# ip_phone_b_miscellaneous.net
KiCad netlist of a schematic drawn in Altium Designer
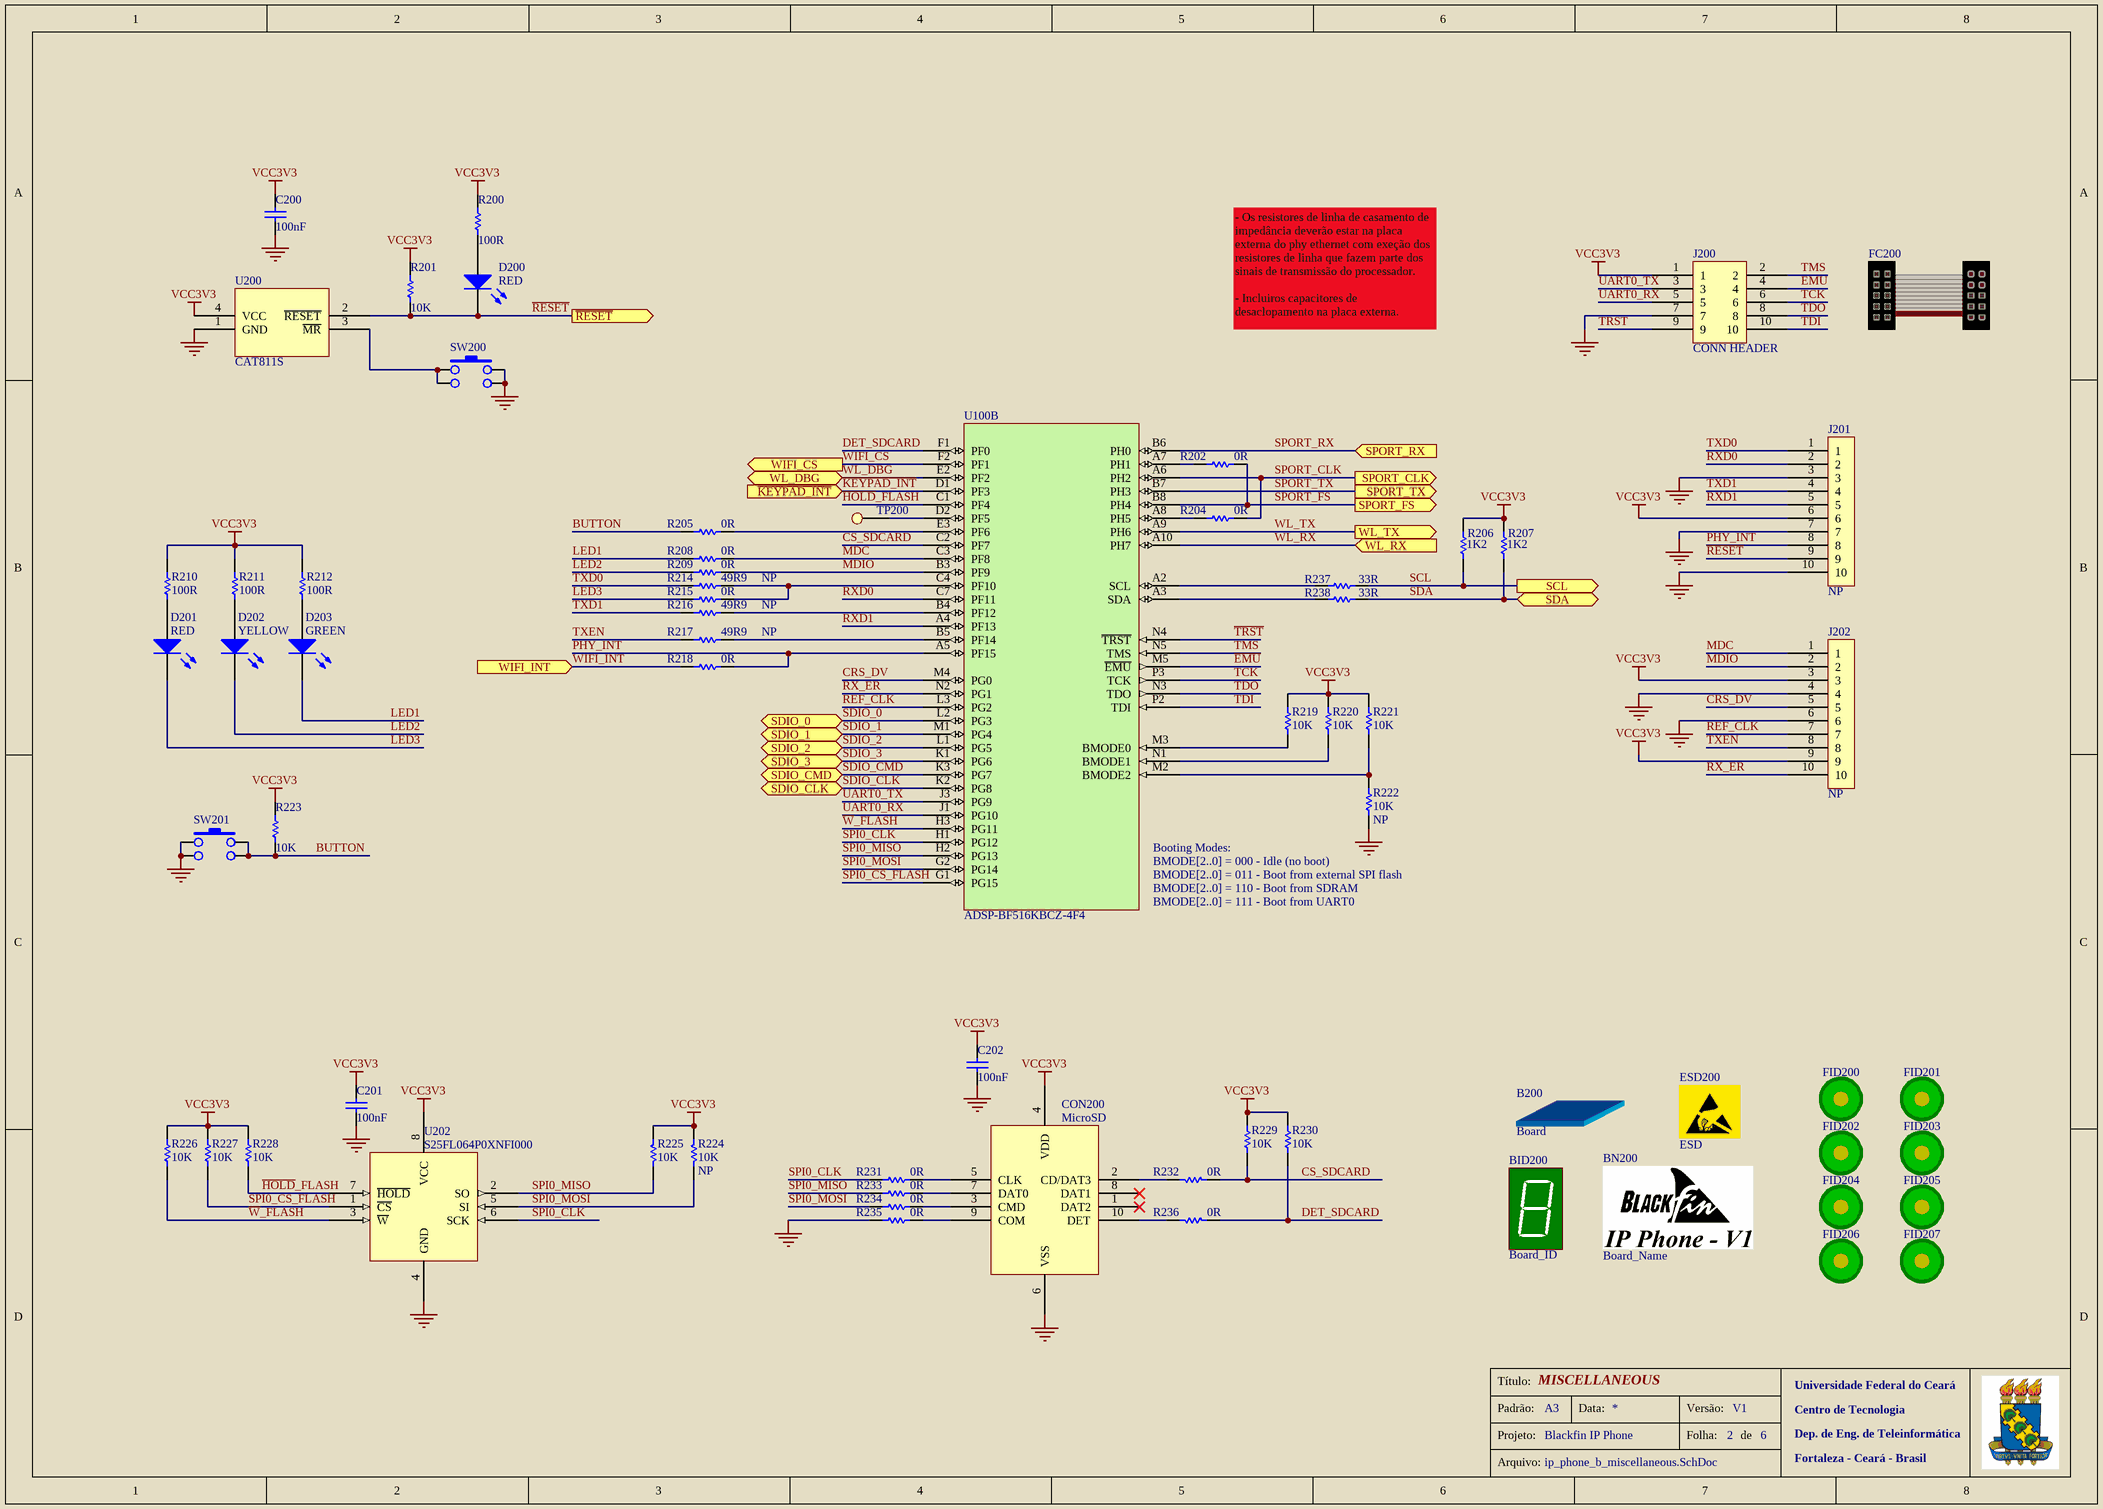
[diagram p0: ip_phone_b_miscellaneous.SchDoc]

(export (version "E")
  (design (tool "Eeschema 10.0.6"))
  (components
    (comp (ref "B200") (value "Board") (libsource (lib "ip_phone") (part "Board")))
    (comp (ref "BID200")
      (value "Board_ID")
      (footprint "ip_phone:BOARD_ID")
      (fields (field (name "EVENDORPART#") "NÃO SE APLICA"))
      (libsource (lib "ip_phone") (part "Board_ID"))
    )
    (comp (ref "BN200")
      (value "Board_Name")
      (footprint "ip_phone:LOGO")
      (fields (field (name "EVENDORPART#") "NÃO SE APLICA"))
      (libsource (lib "ip_phone") (part "Board_Name"))
    )
    (comp (ref "C200")
      (value "100nF")
      (footprint "ip_phone:CC1005-0402")
      (description "MLCC - SMD/SMT 0.1UF 16V 10% 0402")
      (fields (field (name "EVENDORPART#") "810-C1005X7R1C104K") (field (name "MANUFACTURER") "TDK"))
      (libsource (lib "ip_phone") (part "Capacitor"))
    )
    (comp (ref "C201")
      (value "100nF")
      (footprint "ip_phone:CC1005-0402")
      (description "MLCC - SMD/SMT 0.1UF 16V 10% 0402")
      (fields (field (name "EVENDORPART#") "810-C1005X7R1C104K") (field (name "MANUFACTURER") "TDK"))
      (libsource (lib "ip_phone") (part "Capacitor"))
    )
    (comp (ref "C202")
      (value "100nF")
      (footprint "ip_phone:CC1005-0402")
      (description "MLCC - SMD/SMT 0.1UF 16V 10% 0402")
      (fields (field (name "EVENDORPART#") "810-C1005X7R1C104K") (field (name "MANUFACTURER") "TDK"))
      (libsource (lib "ip_phone") (part "Capacitor"))
    )
    (comp (ref "CON200")
      (value "MicroSD")
      (footprint "ip_phone:MICRO_SD")
      (description "CONN MEMORY CARD SD SMD")
      (fields (field (name "MANUFACTURER") "AVX Corporation") (field (name "PART#") "045138008010890+"))
      (libsource (lib "ip_phone") (part "MicroSD"))
    )
    (comp (ref "D200")
      (value "RED")
      (footprint "ip_phone:LED_0603")
      (description "LED")
      (fields (field (name "PART#") "APT1608SURCK") (field (name "MANUFACTURER") "Kingbright"))
      (libsource (lib "ip_phone") (part "LED"))
    )
    (comp (ref "D201")
      (value "RED")
      (footprint "ip_phone:LED 3MM VERMELHO PF-D3")
      (description "LED")
      (fields (field (name "PART#") "TLHR4205") (field (name "MANUFACTURER") "Vishay Semiconductors"))
      (libsource (lib "ip_phone") (part "LED"))
    )
    (comp (ref "D202")
      (value "YELLOW")
      (footprint "ip_phone:LED 3MM AMARELO PF-D3")
      (description "LED")
      (fields (field (name "PART#") "TLHY4205") (field (name "MANUFACTURER") "Vishay Semiconductors"))
      (libsource (lib "ip_phone") (part "LED"))
    )
    (comp (ref "D203")
      (value "GREEN")
      (footprint "ip_phone:LED 3MM VERDE PF-D3")
      (description "LED")
      (fields (field (name "PART#") "TLHG4205") (field (name "MANUFACTURER") "Vishay Semiconductors"))
      (libsource (lib "ip_phone") (part "LED"))
    )
    (comp (ref "ESD200")
      (value "ESD")
      (footprint "ip_phone:ESD")
      (fields (field (name "EVENDORPART#") "NÃO SE APLICA"))
      (libsource (lib "ip_phone") (part "ESD"))
    )
    (comp (ref "FC200")
      (value "Flat Cable")
      (fields (field (name "EVENDORPART#") "SAM8218-ND") (field (name "MANUFACTURER") "Samtec"))
      (libsource (lib "ip_phone") (part "Flat_Cable"))
    )
    (comp (ref "FID200")
      (value "Fiducial")
      (footprint "ip_phone:Fiducial")
      (fields (field (name "EVENDORPART#") "NÃO SE APLICA"))
      (libsource (lib "ip_phone") (part "Fiducial"))
    )
    (comp (ref "FID201")
      (value "Fiducial")
      (footprint "ip_phone:Fiducial")
      (fields (field (name "EVENDORPART#") "NÃO SE APLICA"))
      (libsource (lib "ip_phone") (part "Fiducial"))
    )
    (comp (ref "FID202")
      (value "Fiducial")
      (footprint "ip_phone:Fiducial")
      (fields (field (name "EVENDORPART#") "NÃO SE APLICA"))
      (libsource (lib "ip_phone") (part "Fiducial"))
    )
    (comp (ref "FID203")
      (value "Fiducial")
      (footprint "ip_phone:Fiducial")
      (fields (field (name "EVENDORPART#") "NÃO SE APLICA"))
      (libsource (lib "ip_phone") (part "Fiducial"))
    )
    (comp (ref "FID204")
      (value "Fiducial")
      (footprint "ip_phone:Fiducial")
      (fields (field (name "EVENDORPART#") "NÃO SE APLICA"))
      (libsource (lib "ip_phone") (part "Fiducial"))
    )
    (comp (ref "FID205")
      (value "Fiducial")
      (footprint "ip_phone:Fiducial")
      (fields (field (name "EVENDORPART#") "NÃO SE APLICA"))
      (libsource (lib "ip_phone") (part "Fiducial"))
    )
    (comp (ref "FID206")
      (value "Fiducial")
      (footprint "ip_phone:Fiducial")
      (fields (field (name "EVENDORPART#") "NÃO SE APLICA"))
      (libsource (lib "ip_phone") (part "Fiducial"))
    )
    (comp (ref "FID207")
      (value "Fiducial")
      (footprint "ip_phone:Fiducial")
      (fields (field (name "EVENDORPART#") "NÃO SE APLICA"))
      (libsource (lib "ip_phone") (part "Fiducial"))
    )
    (comp (ref "J200")
      (value "CONN HEADER")
      (footprint "ip_phone:CON_JTAG")
      (description "CONN HEADER .050\" 5x2")
      (fields (field (name "EVENDORPART#") "S9012E-05-ND") (field (name "MANUFACTURER") "Sullins"))
      (libsource (lib "ip_phone") (part "Conector JTAG"))
    )
    (comp (ref "J201")
      (value "CONN HEADER")
      (footprint "ip_phone:CONECTOR_10_PIN")
      (description "CONN HEADER .050\" 10POS PCB GOLD")
      (fields
        (field (name "EVENDORPART#") "S9014E-10-ND")
        (field (name "MANUFACTURER") "Sullins Connector Solutions")
        (field (name "NP") "NP")
      )
      (libsource (lib "ip_phone") (part "Conector 10pin"))
    )
    (comp (ref "J202")
      (value "CONN HEADER")
      (footprint "ip_phone:CONECTOR_10_PIN")
      (description "CONN HEADER .050\" 10POS PCB GOLD")
      (fields
        (field (name "EVENDORPART#") "S9014E-10-ND")
        (field (name "MANUFACTURER") "Sullins Connector Solutions")
        (field (name "NP") "NP")
      )
      (libsource (lib "ip_phone") (part "Conector 10pin"))
    )
    (comp (ref "R200")
      (value "100R")
      (footprint "ip_phone:CR1608-0603")
      (description "Thick Film Resistors 1/16WATT 100R 0402")
      (fields (field (name "EVENDORPART#") "652-CR0603-JW-101GLF") (field (name "MANUFACTURER") "Bourns"))
      (libsource (lib "ip_phone") (part "Resistor"))
    )
    (comp (ref "R201")
      (value "10K")
      (footprint "ip_phone:CR1005-0402")
      (description "Thick Film Resistors SMD 0402 10K 5%  1/16 W")
      (fields (field (name "EVENDORPART#") "311-10KJRCT-ND") (field (name "MANUFACTURER") "Yageo"))
      (libsource (lib "ip_phone") (part "Resistor"))
    )
    (comp (ref "R202")
      (value "0R")
      (footprint "ip_phone:CR1005-0402")
      (description "Thick Film Resistors 0402 1/16W Jumper")
      (fields
        (field (name "EVENDORPART#") "667-ERJ-2GE0R00X")
        (field (name "MANUFACTURER") "Panasonic Electronic Components")
      )
      (libsource (lib "ip_phone") (part "Resistor"))
    )
    (comp (ref "R204")
      (value "0R")
      (footprint "ip_phone:CR1005-0402")
      (description "Thick Film Resistors 0402 1/16W Jumper")
      (fields
        (field (name "EVENDORPART#") "667-ERJ-2GE0R00X")
        (field (name "MANUFACTURER") "Panasonic Electronic Components")
      )
      (libsource (lib "ip_phone") (part "Resistor"))
    )
    (comp (ref "R205")
      (value "0R")
      (footprint "ip_phone:CR1005-0402")
      (description "Thick Film Resistors 0402 1/16W Jumper")
      (fields
        (field (name "EVENDORPART#") "667-ERJ-2GE0R00X")
        (field (name "MANUFACTURER") "Panasonic Electronic Components")
      )
      (libsource (lib "ip_phone") (part "Resistor"))
    )
    (comp (ref "R206")
      (value "1K2")
      (footprint "ip_phone:CR1005-0402")
      (description "Thick Film Resistors SMD 0402 1K2 5%  1/16 W")
      (fields (field (name "EVENDORPART#") "311-1.2KJRCT-ND") (field (name "MANUFACTURER") "Yageo"))
      (libsource (lib "ip_phone") (part "Resistor"))
    )
    (comp (ref "R207")
      (value "1K2")
      (footprint "ip_phone:CR1005-0402")
      (description "Thick Film Resistors SMD 0402 1K2 5%  1/16 W")
      (fields (field (name "EVENDORPART#") "311-1.2KJRCT-ND") (field (name "MANUFACTURER") "Yageo"))
      (libsource (lib "ip_phone") (part "Resistor"))
    )
    (comp (ref "R208")
      (value "0R")
      (footprint "ip_phone:CR1005-0402")
      (description "Thick Film Resistors 0402 1/16W Jumper")
      (fields
        (field (name "EVENDORPART#") "667-ERJ-2GE0R00X")
        (field (name "MANUFACTURER") "Panasonic Electronic Components")
      )
      (libsource (lib "ip_phone") (part "Resistor"))
    )
    (comp (ref "R209")
      (value "0R")
      (footprint "ip_phone:CR1005-0402")
      (description "Thick Film Resistors 0402 1/16W Jumper")
      (fields
        (field (name "EVENDORPART#") "667-ERJ-2GE0R00X")
        (field (name "MANUFACTURER") "Panasonic Electronic Components")
      )
      (libsource (lib "ip_phone") (part "Resistor"))
    )
    (comp (ref "R210")
      (value "100R")
      (footprint "ip_phone:CR1608-0603")
      (description "Thick Film Resistors 1/16WATT 100R 0402")
      (fields (field (name "EVENDORPART#") "652-CR0603-JW-101GLF") (field (name "MANUFACTURER") "Bourns"))
      (libsource (lib "ip_phone") (part "Resistor"))
    )
    (comp (ref "R211")
      (value "100R")
      (footprint "ip_phone:CR1608-0603")
      (description "Thick Film Resistors 1/16WATT 100R 0402")
      (fields (field (name "EVENDORPART#") "652-CR0603-JW-101GLF") (field (name "MANUFACTURER") "Bourns"))
      (libsource (lib "ip_phone") (part "Resistor"))
    )
    (comp (ref "R212")
      (value "100R")
      (footprint "ip_phone:CR1608-0603")
      (description "Thick Film Resistors 1/16WATT 100R 0402")
      (fields (field (name "EVENDORPART#") "652-CR0603-JW-101GLF") (field (name "MANUFACTURER") "Bourns"))
      (libsource (lib "ip_phone") (part "Resistor"))
    )
    (comp (ref "R214")
      (value "49R9")
      (footprint "ip_phone:CR1005-0402_NP")
      (description "Thick Film Resistors - SMD 1/16watt 49.9ohms 1% 0402")
      (fields
        (field (name "EVENDORPART#") "71-CRCW0402-49.9-E3")
        (field (name "MANUFACTURER") "Vishay/Dale")
        (field (name "NP") "NP")
      )
      (libsource (lib "ip_phone") (part "Resistor"))
    )
    (comp (ref "R215")
      (value "0R")
      (footprint "ip_phone:CR1005-0402")
      (description "Thick Film Resistors 0402 1/16W Jumper")
      (fields
        (field (name "EVENDORPART#") "667-ERJ-2GE0R00X")
        (field (name "MANUFACTURER") "Panasonic Electronic Components")
      )
      (libsource (lib "ip_phone") (part "Resistor"))
    )
    (comp (ref "R216")
      (value "49R9")
      (footprint "ip_phone:CR1005-0402_NP")
      (description "Thick Film Resistors - SMD 1/16watt 49.9ohms 1% 0402")
      (fields
        (field (name "EVENDORPART#") "71-CRCW0402-49.9-E3")
        (field (name "MANUFACTURER") "Vishay/Dale")
        (field (name "NP") "NP")
      )
      (libsource (lib "ip_phone") (part "Resistor"))
    )
    (comp (ref "R217")
      (value "49R9")
      (footprint "ip_phone:CR1005-0402_NP")
      (description "Thick Film Resistors - SMD 1/16watt 49.9ohms 1% 0402")
      (fields
        (field (name "EVENDORPART#") "71-CRCW0402-49.9-E3")
        (field (name "MANUFACTURER") "Vishay/Dale")
        (field (name "NP") "NP")
      )
      (libsource (lib "ip_phone") (part "Resistor"))
    )
    (comp (ref "R218")
      (value "0R")
      (footprint "ip_phone:CR1005-0402")
      (description "Thick Film Resistors 0402 1/16W Jumper")
      (fields
        (field (name "EVENDORPART#") "667-ERJ-2GE0R00X")
        (field (name "MANUFACTURER") "Panasonic Electronic Components")
      )
      (libsource (lib "ip_phone") (part "Resistor"))
    )
    (comp (ref "R219")
      (value "10K")
      (footprint "ip_phone:CR1005-0402")
      (description "Thick Film Resistors SMD 0402 10K 5%  1/16 W")
      (fields (field (name "EVENDORPART#") "311-10KJRCT-ND") (field (name "MANUFACTURER") "Yageo"))
      (libsource (lib "ip_phone") (part "Resistor"))
    )
    (comp (ref "R220")
      (value "10K")
      (footprint "ip_phone:CR1005-0402")
      (description "Thick Film Resistors SMD 0402 10K 5%  1/16 W")
      (fields (field (name "EVENDORPART#") "311-10KJRCT-ND") (field (name "MANUFACTURER") "Yageo"))
      (libsource (lib "ip_phone") (part "Resistor"))
    )
    (comp (ref "R221")
      (value "10K")
      (footprint "ip_phone:CR1005-0402")
      (description "Thick Film Resistors SMD 0402 10K 5%  1/16 W")
      (fields (field (name "EVENDORPART#") "311-10KJRCT-ND") (field (name "MANUFACTURER") "Yageo"))
      (libsource (lib "ip_phone") (part "Resistor"))
    )
    (comp (ref "R222")
      (value "10K")
      (footprint "ip_phone:CR1005-0402_NP")
      (description "Thick Film Resistors SMD 0402 10K 5%  1/16 W")
      (fields
        (field (name "EVENDORPART#") "311-10KJRCT-ND")
        (field (name "MANUFACTURER") "Yageo")
        (field (name "NP") "NP")
      )
      (libsource (lib "ip_phone") (part "Resistor"))
    )
    (comp (ref "R223")
      (value "10K")
      (footprint "ip_phone:CR1005-0402")
      (description "Thick Film Resistors SMD 0402 10K 5%  1/16 W")
      (fields (field (name "EVENDORPART#") "311-10KJRCT-ND") (field (name "MANUFACTURER") "Yageo"))
      (libsource (lib "ip_phone") (part "Resistor"))
    )
    (comp (ref "R224")
      (value "10K")
      (footprint "ip_phone:CR1005-0402_NP")
      (description "Thick Film Resistors SMD 0402 10K 5%  1/16 W")
      (fields
        (field (name "EVENDORPART#") "311-10KJRCT-ND")
        (field (name "MANUFACTURER") "Yageo")
        (field (name "NP") "NP")
      )
      (libsource (lib "ip_phone") (part "Resistor"))
    )
    (comp (ref "R225")
      (value "10K")
      (footprint "ip_phone:CR1005-0402")
      (description "Thick Film Resistors SMD 0402 10K 5%  1/16 W")
      (fields (field (name "EVENDORPART#") "311-10KJRCT-ND") (field (name "MANUFACTURER") "Yageo"))
      (libsource (lib "ip_phone") (part "Resistor"))
    )
    (comp (ref "R226")
      (value "10K")
      (footprint "ip_phone:CR1005-0402")
      (description "Thick Film Resistors SMD 0402 10K 5%  1/16 W")
      (fields (field (name "EVENDORPART#") "311-10KJRCT-ND") (field (name "MANUFACTURER") "Yageo"))
      (libsource (lib "ip_phone") (part "Resistor"))
    )
    (comp (ref "R227")
      (value "10K")
      (footprint "ip_phone:CR1005-0402")
      (description "Thick Film Resistors SMD 0402 10K 5%  1/16 W")
      (fields (field (name "EVENDORPART#") "311-10KJRCT-ND") (field (name "MANUFACTURER") "Yageo"))
      (libsource (lib "ip_phone") (part "Resistor"))
    )
    (comp (ref "R228")
      (value "10K")
      (footprint "ip_phone:CR1005-0402")
      (description "Thick Film Resistors SMD 0402 10K 5%  1/16 W")
      (fields (field (name "EVENDORPART#") "311-10KJRCT-ND") (field (name "MANUFACTURER") "Yageo"))
      (libsource (lib "ip_phone") (part "Resistor"))
    )
    (comp (ref "R229")
      (value "10K")
      (footprint "ip_phone:CR1005-0402")
      (description "Thick Film Resistors SMD 0402 10K 5%  1/16 W")
      (fields (field (name "EVENDORPART#") "311-10KJRCT-ND") (field (name "MANUFACTURER") "Yageo"))
      (libsource (lib "ip_phone") (part "Resistor"))
    )
    (comp (ref "R230")
      (value "10K")
      (footprint "ip_phone:CR1005-0402")
      (description "Thick Film Resistors SMD 0402 10K 5%  1/16 W")
      (fields (field (name "EVENDORPART#") "311-10KJRCT-ND") (field (name "MANUFACTURER") "Yageo"))
      (libsource (lib "ip_phone") (part "Resistor"))
    )
    (comp (ref "R231")
      (value "0R")
      (footprint "ip_phone:CR1005-0402")
      (description "Thick Film Resistors 0402 1/16W Jumper")
      (fields
        (field (name "EVENDORPART#") "667-ERJ-2GE0R00X")
        (field (name "MANUFACTURER") "Panasonic Electronic Components")
      )
      (libsource (lib "ip_phone") (part "Resistor"))
    )
    (comp (ref "R232")
      (value "0R")
      (footprint "ip_phone:CR1005-0402")
      (description "Thick Film Resistors 0402 1/16W Jumper")
      (fields
        (field (name "EVENDORPART#") "667-ERJ-2GE0R00X")
        (field (name "MANUFACTURER") "Panasonic Electronic Components")
      )
      (libsource (lib "ip_phone") (part "Resistor"))
    )
    (comp (ref "R233")
      (value "0R")
      (footprint "ip_phone:CR1005-0402")
      (description "Thick Film Resistors 0402 1/16W Jumper")
      (fields
        (field (name "EVENDORPART#") "667-ERJ-2GE0R00X")
        (field (name "MANUFACTURER") "Panasonic Electronic Components")
      )
      (libsource (lib "ip_phone") (part "Resistor"))
    )
    (comp (ref "R234")
      (value "0R")
      (footprint "ip_phone:CR1005-0402")
      (description "Thick Film Resistors 0402 1/16W Jumper")
      (fields
        (field (name "EVENDORPART#") "667-ERJ-2GE0R00X")
        (field (name "MANUFACTURER") "Panasonic Electronic Components")
      )
      (libsource (lib "ip_phone") (part "Resistor"))
    )
    (comp (ref "R235")
      (value "0R")
      (footprint "ip_phone:CR1005-0402")
      (description "Thick Film Resistors 0402 1/16W Jumper")
      (fields
        (field (name "EVENDORPART#") "667-ERJ-2GE0R00X")
        (field (name "MANUFACTURER") "Panasonic Electronic Components")
      )
      (libsource (lib "ip_phone") (part "Resistor"))
    )
    (comp (ref "R236")
      (value "0R")
      (footprint "ip_phone:CR1005-0402")
      (description "Thick Film Resistors 0402 1/16W Jumper")
      (fields
        (field (name "EVENDORPART#") "667-ERJ-2GE0R00X")
        (field (name "MANUFACTURER") "Panasonic Electronic Components")
      )
      (libsource (lib "ip_phone") (part "Resistor"))
    )
    (comp (ref "R237")
      (value "33R")
      (footprint "ip_phone:CR1005-0402")
      (description "Thick Film Resistors SMD 0402 33R 5%  1/16 W")
      (fields (field (name "EVENDORPART#") "311-33JRCT-ND") (field (name "MANUFACTURER") "Yageo"))
      (libsource (lib "ip_phone") (part "Resistor"))
    )
    (comp (ref "R238")
      (value "33R")
      (footprint "ip_phone:CR1005-0402")
      (description "Thick Film Resistors SMD 0402 33R 5%  1/16 W")
      (fields (field (name "EVENDORPART#") "311-33JRCT-ND") (field (name "MANUFACTURER") "Yageo"))
      (libsource (lib "ip_phone") (part "Resistor"))
    )
    (comp (ref "SW200")
      (value "SW")
      (footprint "ip_phone:PUSH-PTS525")
      (description "Switch tact, SMT, SPST, 160gf, 5.25 mm L x 5.25 mm W x 1.5 mm H")
      (fields (field (name "MANUFACTURER") "C&K Components") (field (name "PART#") "PTS525SM10SMTR LFS"))
      (libsource (lib "ip_phone") (part "SWITCH_PUSH_NA_SMD"))
    )
    (comp (ref "SW201")
      (value "SW")
      (footprint "ip_phone:PUSH-PTS525")
      (description "Switch tact, SMT, SPST, 160gf, 5.25 mm L x 5.25 mm W x 1.5 mm H")
      (fields (field (name "MANUFACTURER") "C&K Components") (field (name "PART#") "PTS525SM10SMTR LFS"))
      (libsource (lib "ip_phone") (part "SWITCH_PUSH_NA_SMD"))
    )
    (comp (ref "TP200")
      (value "Test Point")
      (footprint "ip_phone:Test Point")
      (fields (field (name "EVENDORPART#") "NÃO SE APLICA"))
      (libsource (lib "ip_phone") (part "Test Point"))
    )
    (comp (ref "U100")
      (value "ADSP-BF516KBCZ-4F4")
      (footprint "ip_phone:BGA168")
      (description "Low Power Blackfin with Advanced Embedded Connectivity")
      (fields (field (name "MANUFACTURER") "Analog Device"))
      (libsource (lib "ip_phone") (part "ADSP-BF516KBCZ-4F4"))
    )
    (comp (ref "U200")
      (value "CAT811S")
      (footprint "ip_phone:SOT-143")
      (description "IC Supervisor MPU 2.93V  SOT-143")
      (fields (field (name "PART#") "CAT811STBI-GT3") (field (name "MANUFACTURER") "ON Semiconductor"))
      (libsource (lib "ip_phone") (part "CAT811S"))
    )
    (comp (ref "U202")
      (value "S25FL064P0XNFI000")
      (footprint "ip_phone:WSON8")
      (description "Flash Mem Serial-SPI 3V/3.3V 64M-Bit 64M x 1 8ns 8-Pin WSON Tray")
      (fields (field (name "MANUFACTURER") "Spansion"))
      (libsource (lib "ip_phone") (part "S25FL064P0XNFI000"))
    )
  )
  (nets
    (net (code "1") (name "/BUTTON") (class "Default")
      (node (ref "R205") (pin "1") (pinfunction "1_1") (pintype "passive"))
      (node (ref "R223") (pin "1") (pinfunction "1_1") (pintype "passive"))
      (node (ref "SW201") (pin "3") (pinfunction "3_3") (pintype "passive"))
      (node (ref "SW201") (pin "4") (pinfunction "4_4") (pintype "passive"))
    )
    (net (code "2") (name "/CRS_DV") (class "Default")
      (node (ref "J202") (pin "5") (pinfunction "5_5") (pintype "passive"))
      (node (ref "U100") (pin "M4") (pinfunction "PG0_M4") (pintype "bidirectional"))
    )
    (net (code "3") (name "/CS_SDCARD") (class "Default")
      (node (ref "R229") (pin "1") (pinfunction "1_1") (pintype "passive"))
      (node (ref "R232") (pin "1") (pinfunction "1_1") (pintype "passive"))
      (node (ref "U100") (pin "C2") (pinfunction "PF7_C2") (pintype "bidirectional"))
    )
    (net (code "4") (name "/DET_SDCARD") (class "Default")
      (node (ref "R230") (pin "1") (pinfunction "1_1") (pintype "passive"))
      (node (ref "R236") (pin "1") (pinfunction "1_1") (pintype "passive"))
      (node (ref "U100") (pin "F1") (pinfunction "PF0_F1") (pintype "bidirectional"))
    )
    (net (code "5") (name "/LED1") (class "Default")
      (node (ref "D203") (pin "2") (pinfunction "K_2") (pintype "passive"))
      (node (ref "R208") (pin "1") (pinfunction "1_1") (pintype "passive"))
    )
    (net (code "6") (name "/LED2") (class "Default")
      (node (ref "D202") (pin "2") (pinfunction "K_2") (pintype "passive"))
      (node (ref "R209") (pin "1") (pinfunction "1_1") (pintype "passive"))
    )
    (net (code "7") (name "/LED3") (class "Default")
      (node (ref "D201") (pin "2") (pinfunction "K_2") (pintype "passive"))
      (node (ref "R215") (pin "1") (pinfunction "1_1") (pintype "passive"))
    )
    (net (code "8") (name "/MDC") (class "Default")
      (node (ref "J202") (pin "1") (pinfunction "1_1") (pintype "passive"))
      (node (ref "R208") (pin "2") (pinfunction "2_2") (pintype "passive"))
      (node (ref "U100") (pin "C3") (pinfunction "PF8_C3") (pintype "bidirectional"))
    )
    (net (code "9") (name "/MDIO") (class "Default")
      (node (ref "J202") (pin "2") (pinfunction "2_2") (pintype "passive"))
      (node (ref "R209") (pin "2") (pinfunction "2_2") (pintype "passive"))
      (node (ref "U100") (pin "B3") (pinfunction "PF9_B3") (pintype "bidirectional"))
    )
    (net (code "10") (name "/REF_CLK") (class "Default")
      (node (ref "J202") (pin "7") (pinfunction "7_7") (pintype "passive"))
      (node (ref "U100") (pin "L3") (pinfunction "PG2_L3") (pintype "bidirectional"))
    )
    (net (code "11") (name "/RXD0") (class "Default")
      (node (ref "J201") (pin "2") (pinfunction "2_2") (pintype "passive"))
      (node (ref "U100") (pin "C7") (pinfunction "PF11_C7") (pintype "bidirectional"))
    )
    (net (code "12") (name "/RXD1") (class "Default")
      (node (ref "J201") (pin "5") (pinfunction "5_5") (pintype "passive"))
      (node (ref "U100") (pin "A4") (pinfunction "PF13_A4") (pintype "bidirectional"))
    )
    (net (code "13") (name "/RX_ER") (class "Default")
      (node (ref "J202") (pin "10") (pinfunction "10_10") (pintype "passive"))
      (node (ref "U100") (pin "N2") (pinfunction "PG1_N2") (pintype "bidirectional"))
    )
    (net (code "14") (name "/SCL") (class "Default")
      (node (ref "R206") (pin "2") (pinfunction "2_2") (pintype "passive"))
      (node (ref "R237") (pin "2") (pinfunction "2_2") (pintype "passive"))
    )
    (net (code "15") (name "/SDA") (class "Default")
      (node (ref "R207") (pin "2") (pinfunction "2_2") (pintype "passive"))
      (node (ref "R238") (pin "2") (pinfunction "2_2") (pintype "passive"))
    )
    (net (code "16") (name "/SDIO_0") (class "Default")
      (node (ref "U100") (pin "L2") (pinfunction "PG3_L2") (pintype "bidirectional"))
    )
    (net (code "17") (name "/SDIO_1") (class "Default")
      (node (ref "U100") (pin "M1") (pinfunction "PG4_M1") (pintype "bidirectional"))
    )
    (net (code "18") (name "/SDIO_2") (class "Default")
      (node (ref "U100") (pin "L1") (pinfunction "PG5_L1") (pintype "bidirectional"))
    )
    (net (code "19") (name "/SDIO_3") (class "Default")
      (node (ref "U100") (pin "K1") (pinfunction "PG6_K1") (pintype "bidirectional"))
    )
    (net (code "20") (name "/SDIO_CLK") (class "Default")
      (node (ref "U100") (pin "K2") (pinfunction "PG8_K2") (pintype "bidirectional"))
    )
    (net (code "21") (name "/SDIO_CMD") (class "Default")
      (node (ref "U100") (pin "K3") (pinfunction "PG7_K3") (pintype "bidirectional"))
    )
    (net (code "22") (name "/SPI0_CLK") (class "Default")
      (node (ref "R231") (pin "1") (pinfunction "1_1") (pintype "passive"))
      (node (ref "U100") (pin "H1") (pinfunction "PG12_H1") (pintype "bidirectional"))
      (node (ref "U202") (pin "6") (pinfunction "SCK_6") (pintype "input"))
    )
    (net (code "23") (name "/SPI0_MISO") (class "Default")
      (node (ref "R225") (pin "1") (pinfunction "1_1") (pintype "passive"))
      (node (ref "R233") (pin "1") (pinfunction "1_1") (pintype "passive"))
      (node (ref "U100") (pin "H2") (pinfunction "PG13_H2") (pintype "bidirectional"))
      (node (ref "U202") (pin "2") (pinfunction "SO_2") (pintype "output"))
    )
    (net (code "24") (name "/SPI0_MOSI") (class "Default")
      (node (ref "R224") (pin "1") (pinfunction "1_1") (pintype "passive"))
      (node (ref "R234") (pin "1") (pinfunction "1_1") (pintype "passive"))
      (node (ref "U100") (pin "G2") (pinfunction "PG14_G2") (pintype "bidirectional"))
      (node (ref "U202") (pin "5") (pinfunction "SI_5") (pintype "input"))
    )
    (net (code "25") (name "/SPI0~{_CS}_FLASH") (class "Default")
      (node (ref "R227") (pin "1") (pinfunction "1_1") (pintype "passive"))
      (node (ref "U100") (pin "G1") (pinfunction "PG15_G1") (pintype "bidirectional"))
      (node (ref "U202") (pin "1") (pinfunction "~{CS}_1") (pintype "input"))
    )
    (net (code "26") (name "/SPORT_CLK") (class "Default")
      (node (ref "R204") (pin "2") (pinfunction "2_2") (pintype "passive"))
      (node (ref "U100") (pin "A6") (pinfunction "PH2_A6") (pintype "bidirectional"))
    )
    (net (code "27") (name "/SPORT_FS") (class "Default")
      (node (ref "R202") (pin "2") (pinfunction "2_2") (pintype "passive"))
      (node (ref "U100") (pin "B8") (pinfunction "PH4_B8") (pintype "bidirectional"))
    )
    (net (code "28") (name "/SPORT_RX") (class "Default")
      (node (ref "U100") (pin "B6") (pinfunction "PH0_B6") (pintype "bidirectional"))
    )
    (net (code "29") (name "/SPORT_TX") (class "Default")
      (node (ref "U100") (pin "B7") (pinfunction "PH3_B7") (pintype "bidirectional"))
    )
    (net (code "30") (name "/TCK") (class "Default")
      (node (ref "J200") (pin "6") (pinfunction "6_6") (pintype "passive"))
      (node (ref "U100") (pin "P3") (pinfunction "TCK_P3") (pintype "output"))
    )
    (net (code "31") (name "/TDI") (class "Default")
      (node (ref "J200") (pin "10") (pinfunction "10_10") (pintype "passive"))
      (node (ref "U100") (pin "P2") (pinfunction "TDI_P2") (pintype "input"))
    )
    (net (code "32") (name "/TDO") (class "Default")
      (node (ref "J200") (pin "8") (pinfunction "8_8") (pintype "passive"))
      (node (ref "U100") (pin "N3") (pinfunction "TDO_N3") (pintype "output"))
    )
    (net (code "33") (name "/TMS") (class "Default")
      (node (ref "J200") (pin "2") (pinfunction "2_2") (pintype "passive"))
      (node (ref "U100") (pin "N5") (pinfunction "TMS_N5") (pintype "input"))
    )
    (net (code "34") (name "/TXD0") (class "Default")
      (node (ref "J201") (pin "1") (pinfunction "1_1") (pintype "passive"))
      (node (ref "R214") (pin "1") (pinfunction "1_1") (pintype "passive"))
    )
    (net (code "35") (name "/TXD1") (class "Default")
      (node (ref "J201") (pin "4") (pinfunction "4_4") (pintype "passive"))
      (node (ref "R216") (pin "1") (pinfunction "1_1") (pintype "passive"))
    )
    (net (code "36") (name "/TXEN") (class "Default")
      (node (ref "J202") (pin "8") (pinfunction "8_8") (pintype "passive"))
      (node (ref "R217") (pin "1") (pinfunction "1_1") (pintype "passive"))
    )
    (net (code "37") (name "/UART0_RX") (class "Default")
      (node (ref "J200") (pin "5") (pinfunction "5_5") (pintype "passive"))
      (node (ref "U100") (pin "J1") (pinfunction "PG10_J1") (pintype "bidirectional"))
    )
    (net (code "38") (name "/UART0_TX") (class "Default")
      (node (ref "J200") (pin "3") (pinfunction "3_3") (pintype "passive"))
      (node (ref "U100") (pin "J3") (pinfunction "PG9_J3") (pintype "bidirectional"))
    )
    (net (code "39") (name "/WIFI_CS") (class "Default")
      (node (ref "U100") (pin "F2") (pinfunction "PF1_F2") (pintype "bidirectional"))
    )
    (net (code "40") (name "/WIFI_INT") (class "Default")
      (node (ref "R218") (pin "1") (pinfunction "1_1") (pintype "passive"))
    )
    (net (code "41") (name "/WL_DBG") (class "Default")
      (node (ref "U100") (pin "E2") (pinfunction "PF2_E2") (pintype "bidirectional"))
    )
    (net (code "42") (name "/WL_RX") (class "Default")
      (node (ref "U100") (pin "A10") (pinfunction "PH7_A10") (pintype "bidirectional"))
    )
    (net (code "43") (name "/WL_TX") (class "Default")
      (node (ref "U100") (pin "A9") (pinfunction "PH6_A9") (pintype "bidirectional"))
    )
    (net (code "44") (name "/~{EMU}") (class "Default")
      (node (ref "J200") (pin "4") (pinfunction "4_4") (pintype "passive"))
      (node (ref "U100") (pin "M5") (pinfunction "~{EMU}_M5") (pintype "output"))
    )
    (net (code "45") (name "/~{HOLD}_FLASH") (class "Default")
      (node (ref "R228") (pin "1") (pinfunction "1_1") (pintype "passive"))
      (node (ref "U100") (pin "C1") (pinfunction "PF4_C1") (pintype "bidirectional"))
      (node (ref "U202") (pin "7") (pinfunction "~{HOLD}_7") (pintype "input"))
    )
    (net (code "46") (name "/~{KEYPAD_INT}") (class "Default")
      (node (ref "U100") (pin "D1") (pinfunction "PF3_D1") (pintype "bidirectional"))
    )
    (net (code "47") (name "/~{PHY_INT}") (class "Default")
      (node (ref "J201") (pin "8") (pinfunction "8_8") (pintype "passive"))
      (node (ref "R218") (pin "2") (pinfunction "2_2") (pintype "passive"))
      (node (ref "U100") (pin "A5") (pinfunction "PF15_A5") (pintype "bidirectional"))
    )
    (net (code "48") (name "/~{RESET}") (class "Default")
      (node (ref "D200") (pin "2") (pinfunction "K_2") (pintype "passive"))
      (node (ref "J201") (pin "9") (pinfunction "9_9") (pintype "passive"))
      (node (ref "R201") (pin "1") (pinfunction "1_1") (pintype "passive"))
      (node (ref "U200") (pin "2") (pinfunction "~{RESET}_2") (pintype "passive"))
    )
    (net (code "49") (name "/~{TRST}") (class "Default")
      (node (ref "J200") (pin "9") (pinfunction "9_9") (pintype "passive"))
      (node (ref "U100") (pin "N4") (pinfunction "~{TRST}_N4") (pintype "input"))
    )
    (net (code "50") (name "/~{W}_FLASH") (class "Default")
      (node (ref "R226") (pin "1") (pinfunction "1_1") (pintype "passive"))
      (node (ref "U100") (pin "H3") (pinfunction "PG11_H3") (pintype "bidirectional"))
      (node (ref "U202") (pin "3") (pinfunction "~{W}_3") (pintype "input"))
    )
    (net (code "51") (name "GND") (class "Default")
      (node (ref "C200") (pin "1") (pinfunction "1_1") (pintype "passive"))
      (node (ref "C201") (pin "1") (pinfunction "1_1") (pintype "passive"))
      (node (ref "C202") (pin "1") (pinfunction "1_1") (pintype "passive"))
      (node (ref "CON200") (pin "6") (pinfunction "VSS_6") (pintype "passive"))
      (node (ref "J200") (pin "7") (pinfunction "7_7") (pintype "passive"))
      (node (ref "J201") (pin "10") (pinfunction "10_10") (pintype "passive"))
      (node (ref "J201") (pin "3") (pinfunction "3_3") (pintype "passive"))
      (node (ref "J201") (pin "7") (pinfunction "7_7") (pintype "passive"))
      (node (ref "J202") (pin "4") (pinfunction "4_4") (pintype "passive"))
      (node (ref "J202") (pin "6") (pinfunction "6_6") (pintype "passive"))
      (node (ref "R222") (pin "1") (pinfunction "1_1") (pintype "passive"))
      (node (ref "R235") (pin "1") (pinfunction "1_1") (pintype "passive"))
      (node (ref "SW200") (pin "1") (pinfunction "1_1") (pintype "passive"))
      (node (ref "SW200") (pin "2") (pinfunction "2_2") (pintype "passive"))
      (node (ref "SW201") (pin "1") (pinfunction "1_1") (pintype "passive"))
      (node (ref "SW201") (pin "2") (pinfunction "2_2") (pintype "passive"))
      (node (ref "U200") (pin "1") (pinfunction "GND_1") (pintype "passive"))
      (node (ref "U202") (pin "4") (pinfunction "GND_4") (pintype "power_in"))
    )
    (net (code "52") (name "Net-(CON200-CD{slash}DAT3)") (class "Default")
      (node (ref "CON200") (pin "2") (pinfunction "CD/DAT3_2") (pintype "passive"))
      (node (ref "R232") (pin "2") (pinfunction "2_2") (pintype "passive"))
    )
    (net (code "53") (name "Net-(CON200-CLK)") (class "Default")
      (node (ref "CON200") (pin "5") (pinfunction "CLK_5") (pintype "passive"))
      (node (ref "R231") (pin "2") (pinfunction "2_2") (pintype "passive"))
    )
    (net (code "54") (name "Net-(CON200-CMD)") (class "Default")
      (node (ref "CON200") (pin "3") (pinfunction "CMD_3") (pintype "passive"))
      (node (ref "R234") (pin "2") (pinfunction "2_2") (pintype "passive"))
    )
    (net (code "55") (name "Net-(CON200-COM)") (class "Default")
      (node (ref "CON200") (pin "9") (pinfunction "COM_9") (pintype "passive"))
      (node (ref "R235") (pin "2") (pinfunction "2_2") (pintype "passive"))
    )
    (net (code "56") (name "Net-(CON200-DAT0)") (class "Default")
      (node (ref "CON200") (pin "7") (pinfunction "DAT0_7") (pintype "passive"))
      (node (ref "R233") (pin "2") (pinfunction "2_2") (pintype "passive"))
    )
    (net (code "57") (name "Net-(CON200-DET)") (class "Default")
      (node (ref "CON200") (pin "10") (pinfunction "DET_10") (pintype "passive"))
      (node (ref "R236") (pin "2") (pinfunction "2_2") (pintype "passive"))
    )
    (net (code "58") (name "Net-(D200-A)") (class "Default")
      (node (ref "D200") (pin "1") (pinfunction "A_1") (pintype "passive"))
      (node (ref "R200") (pin "1") (pinfunction "1_1") (pintype "passive"))
    )
    (net (code "59") (name "Net-(D201-A)") (class "Default")
      (node (ref "D201") (pin "1") (pinfunction "A_1") (pintype "passive"))
      (node (ref "R210") (pin "1") (pinfunction "1_1") (pintype "passive"))
    )
    (net (code "60") (name "Net-(D202-A)") (class "Default")
      (node (ref "D202") (pin "1") (pinfunction "A_1") (pintype "passive"))
      (node (ref "R211") (pin "1") (pinfunction "1_1") (pintype "passive"))
    )
    (net (code "61") (name "Net-(D203-A)") (class "Default")
      (node (ref "D203") (pin "1") (pinfunction "A_1") (pintype "passive"))
      (node (ref "R212") (pin "1") (pinfunction "1_1") (pintype "passive"))
    )
    (net (code "62") (name "Net-(U100B-BMODE0)") (class "Default")
      (node (ref "R219") (pin "1") (pinfunction "1_1") (pintype "passive"))
      (node (ref "U100") (pin "M3") (pinfunction "BMODE0_M3") (pintype "input"))
    )
    (net (code "63") (name "Net-(U100B-BMODE1)") (class "Default")
      (node (ref "R220") (pin "1") (pinfunction "1_1") (pintype "passive"))
      (node (ref "U100") (pin "N1") (pinfunction "BMODE1_N1") (pintype "input"))
    )
    (net (code "64") (name "Net-(U100B-BMODE2)") (class "Default")
      (node (ref "R221") (pin "1") (pinfunction "1_1") (pintype "passive"))
      (node (ref "R222") (pin "2") (pinfunction "2_2") (pintype "passive"))
      (node (ref "U100") (pin "M2") (pinfunction "BMODE2_M2") (pintype "input"))
    )
    (net (code "65") (name "Net-(U100B-PF5)") (class "Default")
      (node (ref "TP200") (pin "1") (pinfunction "1_1") (pintype "passive"))
      (node (ref "U100") (pin "D2") (pinfunction "PF5_D2") (pintype "bidirectional"))
    )
    (net (code "66") (name "Net-(U100B-PF6)") (class "Default")
      (node (ref "R205") (pin "2") (pinfunction "2_2") (pintype "passive"))
      (node (ref "U100") (pin "E3") (pinfunction "PF6_E3") (pintype "bidirectional"))
    )
    (net (code "67") (name "Net-(U100B-PF10)") (class "Default")
      (node (ref "R214") (pin "2") (pinfunction "2_2") (pintype "passive"))
      (node (ref "R215") (pin "2") (pinfunction "2_2") (pintype "passive"))
      (node (ref "U100") (pin "C4") (pinfunction "PF10_C4") (pintype "bidirectional"))
    )
    (net (code "68") (name "Net-(U100B-PF12)") (class "Default")
      (node (ref "R216") (pin "2") (pinfunction "2_2") (pintype "passive"))
      (node (ref "U100") (pin "B4") (pinfunction "PF12_B4") (pintype "bidirectional"))
    )
    (net (code "69") (name "Net-(U100B-PF14)") (class "Default")
      (node (ref "R217") (pin "2") (pinfunction "2_2") (pintype "passive"))
      (node (ref "U100") (pin "B5") (pinfunction "PF14_B5") (pintype "bidirectional"))
    )
    (net (code "70") (name "Net-(U100B-PH1)") (class "Default")
      (node (ref "R202") (pin "1") (pinfunction "1_1") (pintype "passive"))
      (node (ref "U100") (pin "A7") (pinfunction "PH1_A7") (pintype "bidirectional"))
    )
    (net (code "71") (name "Net-(U100B-PH5)") (class "Default")
      (node (ref "R204") (pin "1") (pinfunction "1_1") (pintype "passive"))
      (node (ref "U100") (pin "A8") (pinfunction "PH5_A8") (pintype "bidirectional"))
    )
    (net (code "72") (name "Net-(U100B-SCL)") (class "Default")
      (node (ref "R237") (pin "1") (pinfunction "1_1") (pintype "passive"))
      (node (ref "U100") (pin "A2") (pinfunction "SCL_A2") (pintype "bidirectional"))
    )
    (net (code "73") (name "Net-(U100B-SDA)") (class "Default")
      (node (ref "R238") (pin "1") (pinfunction "1_1") (pintype "passive"))
      (node (ref "U100") (pin "A3") (pinfunction "SDA_A3") (pintype "bidirectional"))
    )
    (net (code "74") (name "Net-(U200-~{MR})") (class "Default")
      (node (ref "SW200") (pin "3") (pinfunction "3_3") (pintype "passive"))
      (node (ref "SW200") (pin "4") (pinfunction "4_4") (pintype "passive"))
      (node (ref "U200") (pin "3") (pinfunction "~{MR}_3") (pintype "passive"))
    )
    (net (code "75") (name "VCC3V3") (class "Default")
      (node (ref "C200") (pin "2") (pinfunction "2_2") (pintype "passive"))
      (node (ref "C201") (pin "2") (pinfunction "2_2") (pintype "passive"))
      (node (ref "C202") (pin "2") (pinfunction "2_2") (pintype "passive"))
      (node (ref "CON200") (pin "4") (pinfunction "VDD_4") (pintype "passive"))
      (node (ref "J200") (pin "1") (pinfunction "1_1") (pintype "passive"))
      (node (ref "J201") (pin "6") (pinfunction "6_6") (pintype "passive"))
      (node (ref "J202") (pin "3") (pinfunction "3_3") (pintype "passive"))
      (node (ref "J202") (pin "9") (pinfunction "9_9") (pintype "passive"))
      (node (ref "R200") (pin "2") (pinfunction "2_2") (pintype "passive"))
      (node (ref "R201") (pin "2") (pinfunction "2_2") (pintype "passive"))
      (node (ref "R206") (pin "1") (pinfunction "1_1") (pintype "passive"))
      (node (ref "R207") (pin "1") (pinfunction "1_1") (pintype "passive"))
      (node (ref "R210") (pin "2") (pinfunction "2_2") (pintype "passive"))
      (node (ref "R211") (pin "2") (pinfunction "2_2") (pintype "passive"))
      (node (ref "R212") (pin "2") (pinfunction "2_2") (pintype "passive"))
      (node (ref "R219") (pin "2") (pinfunction "2_2") (pintype "passive"))
      (node (ref "R220") (pin "2") (pinfunction "2_2") (pintype "passive"))
      (node (ref "R221") (pin "2") (pinfunction "2_2") (pintype "passive"))
      (node (ref "R223") (pin "2") (pinfunction "2_2") (pintype "passive"))
      (node (ref "R224") (pin "2") (pinfunction "2_2") (pintype "passive"))
      (node (ref "R225") (pin "2") (pinfunction "2_2") (pintype "passive"))
      (node (ref "R226") (pin "2") (pinfunction "2_2") (pintype "passive"))
      (node (ref "R227") (pin "2") (pinfunction "2_2") (pintype "passive"))
      (node (ref "R228") (pin "2") (pinfunction "2_2") (pintype "passive"))
      (node (ref "R229") (pin "2") (pinfunction "2_2") (pintype "passive"))
      (node (ref "R230") (pin "2") (pinfunction "2_2") (pintype "passive"))
      (node (ref "U200") (pin "4") (pinfunction "VCC_4") (pintype "passive"))
      (node (ref "U202") (pin "8") (pinfunction "VCC_8") (pintype "power_in"))
    )
    (net (code "76") (name "unconnected-(CON200-DAT1-Pad8)") (class "Default")
      (node (ref "CON200") (pin "8") (pinfunction "DAT1_8") (pintype "passive+no_connect"))
    )
    (net (code "77") (name "unconnected-(CON200-DAT2-Pad1)") (class "Default")
      (node (ref "CON200") (pin "1") (pinfunction "DAT2_1") (pintype "passive+no_connect"))
    )
  )
)
